# SQUID_Channel_DACS.net
KiCad netlist of a schematic drawn in Altium Designer
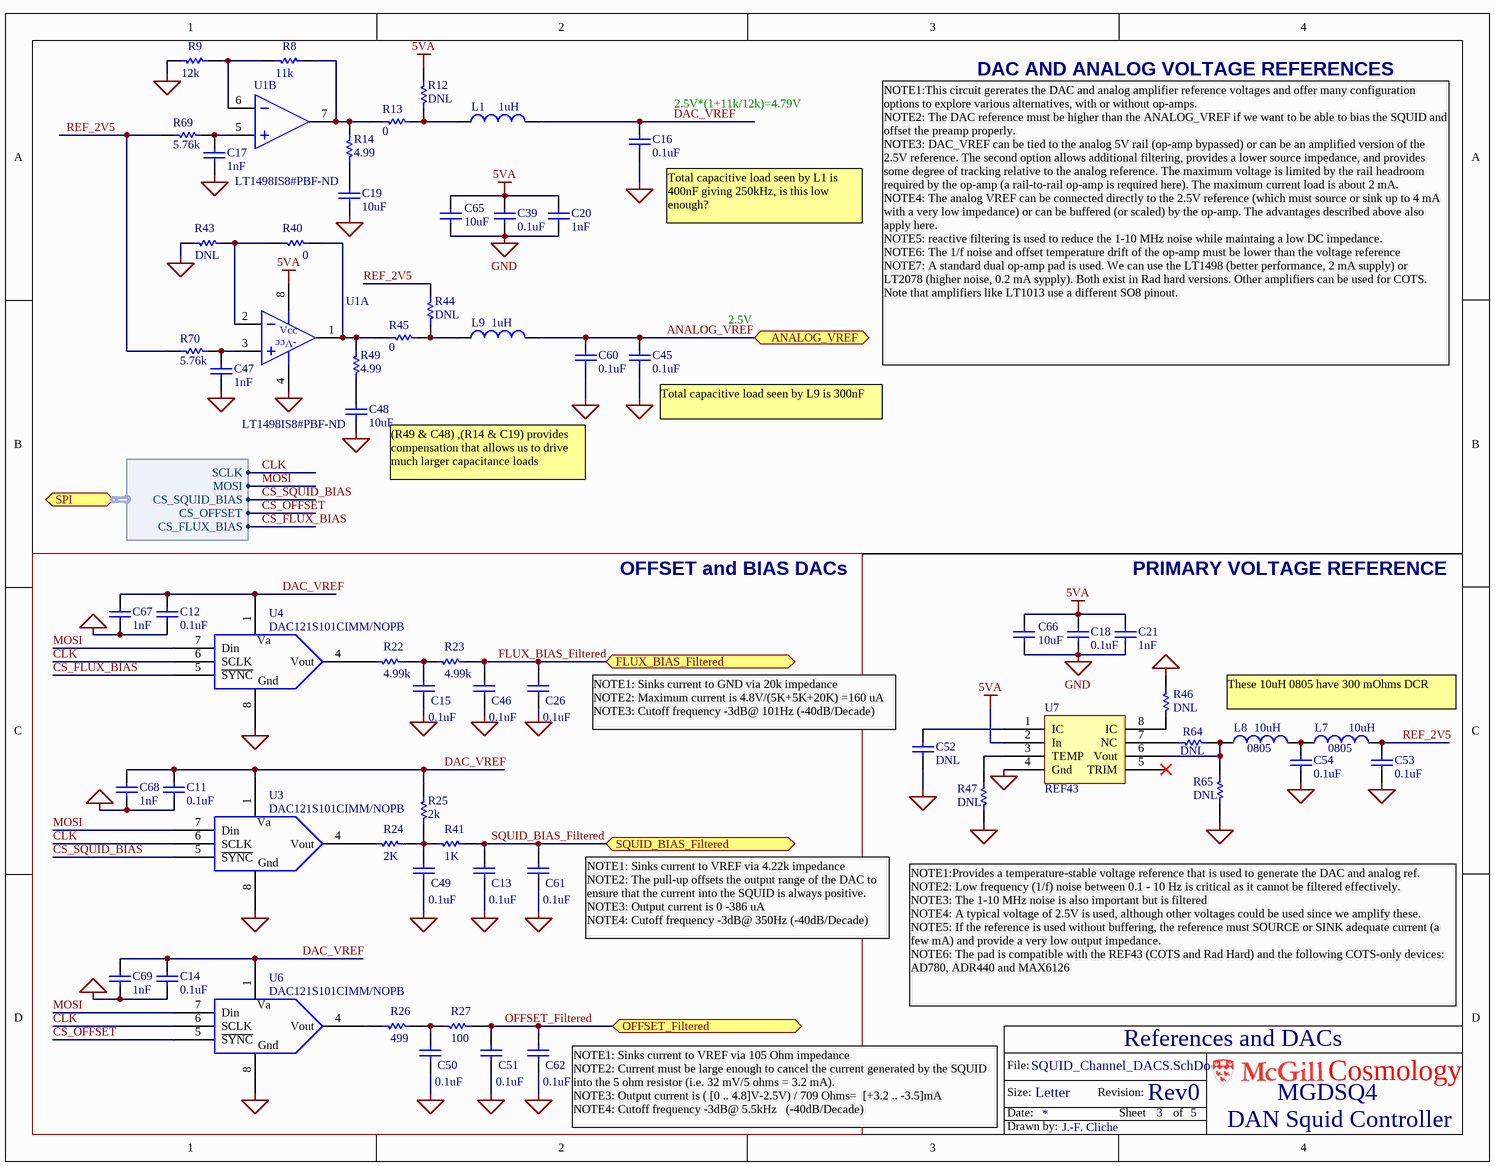
[diagram p0: SQUID_Channel_DACS.SchDoc]

(export (version "E")
  (design (tool "Eeschema 10.0.6"))
  (components
    (comp (ref "C11")
      (value "0.1uF")
      (footprint "0603")
      (description "Capacitor, Ceramic, 0603")
      (fields (field (name "MANUFACTURER") "Generic"))
      (libsource (lib "MiniSquidCtrl") (part "Cap0603"))
    )
    (comp (ref "C12")
      (value "0.1uF")
      (footprint "0603")
      (description "Capacitor, Ceramic, 0603")
      (fields (field (name "MANUFACTURER") "Generic"))
      (libsource (lib "MiniSquidCtrl") (part "Cap0603"))
    )
    (comp (ref "C13")
      (value "0.1uF")
      (footprint "0603")
      (description "Capacitor, Ceramic, 0603")
      (fields (field (name "MANUFACTURER") "Generic"))
      (libsource (lib "MiniSquidCtrl") (part "Cap0603"))
    )
    (comp (ref "C14")
      (value "0.1uF")
      (footprint "0603")
      (description "Capacitor, Ceramic, 0603")
      (fields (field (name "MANUFACTURER") "Generic"))
      (libsource (lib "MiniSquidCtrl") (part "Cap0603"))
    )
    (comp (ref "C15")
      (value "0.1uF")
      (footprint "0603")
      (description "Capacitor, Ceramic, 0603")
      (fields (field (name "MANUFACTURER") "Generic"))
      (libsource (lib "MiniSquidCtrl") (part "Cap0603"))
    )
    (comp (ref "C16")
      (value "0.1uF")
      (footprint "0603")
      (description "Capacitor, Ceramic, 0603")
      (fields (field (name "MANUFACTURER") "Generic"))
      (libsource (lib "MiniSquidCtrl") (part "Cap0603"))
    )
    (comp (ref "C17")
      (value "1nF")
      (footprint "0603")
      (description "Capacitor, Ceramic, 0603")
      (fields (field (name "MANUFACTURER") "Generic"))
      (libsource (lib "MiniSquidCtrl") (part "Cap0603"))
    )
    (comp (ref "C18")
      (value "0.1uF")
      (footprint "0603")
      (description "Capacitor, Ceramic, 0603")
      (fields (field (name "MANUFACTURER") "Generic"))
      (libsource (lib "MiniSquidCtrl") (part "Cap0603"))
    )
    (comp (ref "C19")
      (value "10uF")
      (footprint "0603")
      (description "Capacitor, Ceramic, 0603")
      (fields (field (name "MANUFACTURER") "Generic"))
      (libsource (lib "MiniSquidCtrl") (part "Cap0603"))
    )
    (comp (ref "C20")
      (value "1nF")
      (footprint "0603")
      (description "Capacitor, Ceramic, 0603")
      (fields (field (name "MANUFACTURER") "Generic"))
      (libsource (lib "MiniSquidCtrl") (part "Cap0603"))
    )
    (comp (ref "C21")
      (value "1nF")
      (footprint "0603")
      (description "Capacitor, Ceramic, 0603")
      (fields (field (name "MANUFACTURER") "Generic"))
      (libsource (lib "MiniSquidCtrl") (part "Cap0603"))
    )
    (comp (ref "C26")
      (value "0.1uF")
      (footprint "0603")
      (description "Capacitor, Ceramic, 0603")
      (fields (field (name "MANUFACTURER") "Generic"))
      (libsource (lib "MiniSquidCtrl") (part "Cap0603"))
    )
    (comp (ref "C39")
      (value "0.1uF")
      (footprint "0603")
      (description "Capacitor, Ceramic, 0603")
      (fields (field (name "MANUFACTURER") "Generic"))
      (libsource (lib "MiniSquidCtrl") (part "Cap0603"))
    )
    (comp (ref "C45")
      (value "0.1uF")
      (footprint "0603")
      (description "Capacitor, Ceramic, 0603")
      (fields (field (name "MANUFACTURER") "Generic"))
      (libsource (lib "MiniSquidCtrl") (part "Cap0603"))
    )
    (comp (ref "C46")
      (value "0.1uF")
      (footprint "0603")
      (description "Capacitor, Ceramic, 0603")
      (fields (field (name "MANUFACTURER") "Generic"))
      (libsource (lib "MiniSquidCtrl") (part "Cap0603"))
    )
    (comp (ref "C47")
      (value "1nF")
      (footprint "0603")
      (description "Capacitor, Ceramic, 0603")
      (fields (field (name "MANUFACTURER") "Generic"))
      (libsource (lib "MiniSquidCtrl") (part "Cap0603"))
    )
    (comp (ref "C48")
      (value "10uF")
      (footprint "0603")
      (description "Capacitor, Ceramic, 0603")
      (fields (field (name "MANUFACTURER") "Generic"))
      (libsource (lib "MiniSquidCtrl") (part "Cap0603"))
    )
    (comp (ref "C49")
      (value "0.1uF")
      (footprint "0603")
      (description "Capacitor, Ceramic, 0603")
      (fields (field (name "MANUFACTURER") "Generic"))
      (libsource (lib "MiniSquidCtrl") (part "Cap0603"))
    )
    (comp (ref "C50")
      (value "0.1uF")
      (footprint "0603")
      (description "Capacitor, Ceramic, 0603")
      (fields (field (name "MANUFACTURER") "Generic"))
      (libsource (lib "MiniSquidCtrl") (part "Cap0603"))
    )
    (comp (ref "C51")
      (value "0.1uF")
      (footprint "0603")
      (description "Capacitor, Ceramic, 0603")
      (fields (field (name "MANUFACTURER") "Generic"))
      (libsource (lib "MiniSquidCtrl") (part "Cap0603"))
    )
    (comp (ref "C52")
      (value "DNL")
      (footprint "0603")
      (description "Capacitor, Ceramic, 0603")
      (fields (field (name "MANUFACTURER") "Generic"))
      (libsource (lib "MiniSquidCtrl") (part "Cap0603"))
    )
    (comp (ref "C53")
      (value "0.1uF")
      (footprint "0603")
      (description "Capacitor, Ceramic, 0603")
      (fields (field (name "MANUFACTURER") "Generic"))
      (libsource (lib "MiniSquidCtrl") (part "Cap0603"))
    )
    (comp (ref "C54")
      (value "0.1uF")
      (footprint "0603")
      (description "Capacitor, Ceramic, 0603")
      (fields (field (name "MANUFACTURER") "Generic"))
      (libsource (lib "MiniSquidCtrl") (part "Cap0603"))
    )
    (comp (ref "C60")
      (value "0.1uF")
      (footprint "0603")
      (description "Capacitor, Ceramic, 0603")
      (fields (field (name "MANUFACTURER") "Generic"))
      (libsource (lib "MiniSquidCtrl") (part "Cap0603"))
    )
    (comp (ref "C61")
      (value "0.1uF")
      (footprint "0603")
      (description "Capacitor, Ceramic, 0603")
      (fields (field (name "MANUFACTURER") "Generic"))
      (libsource (lib "MiniSquidCtrl") (part "Cap0603"))
    )
    (comp (ref "C62")
      (value "0.1uF")
      (footprint "0603")
      (description "Capacitor, Ceramic, 0603")
      (fields (field (name "MANUFACTURER") "Generic"))
      (libsource (lib "MiniSquidCtrl") (part "Cap0603"))
    )
    (comp (ref "C65")
      (value "10uF")
      (footprint "CC3225-1210")
      (description "Capacitor, Ceramic, 1210")
      (fields (field (name "MANUFACTURER PART NUMBER") "1206YD106KAT2A") (field (name "VOLTAGE") "16V"))
      (libsource (lib "MiniSquidCtrl") (part "CAP 1210"))
    )
    (comp (ref "C66")
      (value "10uF")
      (footprint "CC3225-1210")
      (description "Capacitor, Ceramic, 1210")
      (fields (field (name "MANUFACTURER PART NUMBER") "1206YD106KAT2A") (field (name "VOLTAGE") "16V"))
      (libsource (lib "MiniSquidCtrl") (part "CAP 1210"))
    )
    (comp (ref "C67")
      (value "1nF")
      (footprint "0603")
      (description "Capacitor, Ceramic, 0603")
      (fields (field (name "MANUFACTURER") "Generic"))
      (libsource (lib "MiniSquidCtrl") (part "Cap0603"))
    )
    (comp (ref "C68")
      (value "1nF")
      (footprint "0603")
      (description "Capacitor, Ceramic, 0603")
      (fields (field (name "MANUFACTURER") "Generic"))
      (libsource (lib "MiniSquidCtrl") (part "Cap0603"))
    )
    (comp (ref "C69")
      (value "1nF")
      (footprint "0603")
      (description "Capacitor, Ceramic, 0603")
      (fields (field (name "MANUFACTURER") "Generic"))
      (libsource (lib "MiniSquidCtrl") (part "Cap0603"))
    )
    (comp (ref "L1")
      (value "1uH")
      (footprint "0603")
      (description "Inductor 0603")
      (fields (field (name "MANUFACTURER") "TDK Corporation"))
      (libsource (lib "MiniSquidCtrl") (part "Inductor0603"))
    )
    (comp (ref "L7")
      (value "10uH")
      (footprint "0805")
      (description "Inductor 0805")
      (fields (field (name "INDUCTANCE") "10uH") (field (name "MANUFACTURER") "TDK Corporation"))
      (libsource (lib "MiniSquidCtrl") (part "Inductor0603"))
    )
    (comp (ref "L8")
      (value "10uH")
      (footprint "0805")
      (description "Inductor 0805")
      (fields (field (name "INDUCTANCE") "10uH") (field (name "MANUFACTURER") "TDK Corporation"))
      (libsource (lib "MiniSquidCtrl") (part "Inductor0603"))
    )
    (comp (ref "L9")
      (value "1uH")
      (footprint "0603")
      (description "Inductor 0603")
      (fields (field (name "MANUFACTURER") "TDK Corporation"))
      (libsource (lib "MiniSquidCtrl") (part "Inductor0603"))
    )
    (comp (ref "R8")
      (value "11k")
      (footprint "0603")
      (description "RES 0603")
      (fields (field (name "MANUFACTURER") "Generic"))
      (libsource (lib "MiniSquidCtrl") (part "Res0603"))
    )
    (comp (ref "R9")
      (value "12k")
      (footprint "0603")
      (description "RES 0603")
      (fields (field (name "MANUFACTURER") "Generic"))
      (libsource (lib "MiniSquidCtrl") (part "RES 0603"))
    )
    (comp (ref "R12")
      (value "DNL")
      (footprint "0603")
      (description "RES 0603")
      (fields (field (name "MANUFACTURER") "Generic"))
      (libsource (lib "MiniSquidCtrl") (part "Res0603"))
    )
    (comp (ref "R13")
      (value "0")
      (footprint "0603")
      (description "RES 0603")
      (fields (field (name "MANUFACTURER") "Generic"))
      (libsource (lib "MiniSquidCtrl") (part "Res0603"))
    )
    (comp (ref "R14")
      (value "4.99")
      (footprint "0603")
      (description "RES 0603")
      (fields (field (name "MANUFACTURER") "Generic"))
      (libsource (lib "MiniSquidCtrl") (part "Res0603"))
    )
    (comp (ref "R22")
      (value "4.99k")
      (footprint "0603")
      (description "RES 0603")
      (fields (field (name "MANUFACTURER") "Generic"))
      (libsource (lib "MiniSquidCtrl") (part "Res0603"))
    )
    (comp (ref "R23")
      (value "4.99k")
      (footprint "0603")
      (description "RES 0603")
      (fields (field (name "MANUFACTURER") "Generic"))
      (libsource (lib "MiniSquidCtrl") (part "Res0603"))
    )
    (comp (ref "R24")
      (value "2K")
      (footprint "0603")
      (description "RES 0603")
      (fields (field (name "MANUFACTURER") "Generic") (field (name "Comment") "2k"))
      (libsource (lib "MiniSquidCtrl") (part "Res0603"))
    )
    (comp (ref "R25")
      (value "2k")
      (footprint "0603")
      (description "RES 0603")
      (fields (field (name "MANUFACTURER") "Generic"))
      (libsource (lib "MiniSquidCtrl") (part "Res0603"))
    )
    (comp (ref "R26")
      (value "499")
      (footprint "0603")
      (description "RES 0603")
      (fields (field (name "MANUFACTURER") "Generic"))
      (libsource (lib "MiniSquidCtrl") (part "Res0603"))
    )
    (comp (ref "R27")
      (value "100")
      (footprint "0603")
      (description "RES 0603")
      (fields (field (name "MANUFACTURER") "Generic"))
      (libsource (lib "MiniSquidCtrl") (part "Res0603"))
    )
    (comp (ref "R40")
      (value "0")
      (footprint "0603")
      (description "RES 0603")
      (fields (field (name "MANUFACTURER") "Generic"))
      (libsource (lib "MiniSquidCtrl") (part "Res0603"))
    )
    (comp (ref "R41")
      (value "1K")
      (footprint "0603")
      (description "RES 0603")
      (fields (field (name "MANUFACTURER") "Generic") (field (name "Comment") "1k"))
      (libsource (lib "MiniSquidCtrl") (part "Res0603"))
    )
    (comp (ref "R43")
      (value "DNL")
      (footprint "0603")
      (description "RES 0603")
      (fields (field (name "MANUFACTURER") "Generic"))
      (libsource (lib "MiniSquidCtrl") (part "RES 0603"))
    )
    (comp (ref "R44")
      (value "DNL")
      (footprint "0603")
      (description "RES 0603")
      (fields (field (name "MANUFACTURER") "Generic"))
      (libsource (lib "MiniSquidCtrl") (part "Res0603"))
    )
    (comp (ref "R45")
      (value "0")
      (footprint "0603")
      (description "RES 0603")
      (fields (field (name "MANUFACTURER") "Generic"))
      (libsource (lib "MiniSquidCtrl") (part "Res0603"))
    )
    (comp (ref "R46")
      (value "DNL")
      (footprint "0603")
      (description "RES 0603")
      (fields (field (name "TOLERANCE") "1%") (field (name "POWER") "1/10W"))
      (libsource (lib "MiniSquidCtrl") (part "RES 0603"))
    )
    (comp (ref "R47")
      (value "DNL")
      (footprint "0603")
      (description "RES 0603")
      (fields (field (name "MANUFACTURER") "Generic"))
      (libsource (lib "MiniSquidCtrl") (part "RES 0603"))
    )
    (comp (ref "R49")
      (value "4.99")
      (footprint "0603")
      (description "RES 0603")
      (fields (field (name "MANUFACTURER") "Generic"))
      (libsource (lib "MiniSquidCtrl") (part "Res0603"))
    )
    (comp (ref "R64")
      (value "DNL")
      (footprint "0603")
      (description "RES 0603")
      (fields (field (name "MANUFACTURER") "Generic"))
      (libsource (lib "MiniSquidCtrl") (part "RES 0603"))
    )
    (comp (ref "R65")
      (value "DNL")
      (footprint "0603")
      (description "RES 0603")
      (fields (field (name "MANUFACTURER") "Generic"))
      (libsource (lib "MiniSquidCtrl") (part "RES 0603"))
    )
    (comp (ref "R69")
      (value "5.76k")
      (footprint "0603")
      (description "RES 0603")
      (fields (field (name "MANUFACTURER") "Generic"))
      (libsource (lib "MiniSquidCtrl") (part "Res0603"))
    )
    (comp (ref "R70")
      (value "5.76k")
      (footprint "0603")
      (description "RES 0603")
      (fields (field (name "MANUFACTURER") "Generic"))
      (libsource (lib "MiniSquidCtrl") (part "Res0603"))
    )
    (comp (ref "U1")
      (value "LT1498IS8#PBF-ND")
      (footprint "SO8")
      (description "IC OP AMP DUAL 2CH LN 8-SOIC")
      (fields (field (name "MANUFACTURER") "National Semiconductor"))
      (libsource (lib "MiniSquidCtrl") (part "LMH6628"))
    )
    (comp (ref "U3")
      (value "DAC121S101CIMM/NOPB")
      (footprint "MSOP-8")
      (description "CONV D/A 12BIT MICROPWR 8MSOP")
      (fields (field (name "MANUFACTURER") "National Semiconductor"))
      (libsource (lib "MiniSquidCtrl") (part "DAC121S101CIMM/NOPB"))
    )
    (comp (ref "U4")
      (value "DAC121S101CIMM/NOPB")
      (footprint "MSOP-8")
      (description "CONV D/A 12BIT MICROPWR 8MSOP")
      (fields (field (name "MANUFACTURER") "National Semiconductor"))
      (libsource (lib "MiniSquidCtrl") (part "DAC121S101CIMM/NOPB"))
    )
    (comp (ref "U6")
      (value "DAC121S101CIMM/NOPB")
      (footprint "MSOP-8")
      (description "CONV D/A 12BIT MICROPWR 8MSOP")
      (fields (field (name "MANUFACTURER") "National Semiconductor"))
      (libsource (lib "MiniSquidCtrl") (part "DAC121S101CIMM/NOPB"))
    )
    (comp (ref "U7")
      (value "REF43")
      (footprint "SO8")
      (description "Voltage Referance")
      (libsource (lib "MiniSquidCtrl") (part "REF43"))
    )
  )
  (nets
    (net (code "2") (name "/ANALOG_VREF") (class "Default")
      (node (ref "C45") (pin "2") (pinfunction "2_2") (pintype "passive"))
      (node (ref "C60") (pin "2") (pinfunction "2_2") (pintype "passive"))
      (node (ref "L9") (pin "1") (pinfunction "1_1") (pintype "passive"))
    )
    (net (code "3") (name "/CLK") (class "Default")
      (node (ref "U3") (pin "6") (pinfunction "SCLK_6") (pintype "passive"))
      (node (ref "U4") (pin "6") (pinfunction "SCLK_6") (pintype "passive"))
      (node (ref "U6") (pin "6") (pinfunction "SCLK_6") (pintype "passive"))
    )
    (net (code "4") (name "/CS_FLUX_BIAS") (class "Default")
      (node (ref "U4") (pin "5") (pinfunction "~{SYNC}_5") (pintype "passive"))
    )
    (net (code "5") (name "/CS_OFFSET") (class "Default")
      (node (ref "U6") (pin "5") (pinfunction "~{SYNC}_5") (pintype "passive"))
    )
    (net (code "6") (name "/CS_SQUID_BIAS") (class "Default")
      (node (ref "U3") (pin "5") (pinfunction "~{SYNC}_5") (pintype "passive"))
    )
    (net (code "7") (name "/DAC_VREF") (class "Default")
      (node (ref "C11") (pin "1") (pinfunction "1_1") (pintype "passive"))
      (node (ref "C12") (pin "1") (pinfunction "1_1") (pintype "passive"))
      (node (ref "C14") (pin "2") (pinfunction "2_2") (pintype "passive"))
      (node (ref "C16") (pin "2") (pinfunction "2_2") (pintype "passive"))
      (node (ref "C67") (pin "2") (pinfunction "2_2") (pintype "passive"))
      (node (ref "C68") (pin "2") (pinfunction "2_2") (pintype "passive"))
      (node (ref "C69") (pin "2") (pinfunction "2_2") (pintype "passive"))
      (node (ref "L1") (pin "1") (pinfunction "1_1") (pintype "passive"))
      (node (ref "R25") (pin "2") (pinfunction "2_2") (pintype "passive"))
      (node (ref "U3") (pin "1") (pinfunction "Va_1") (pintype "passive"))
      (node (ref "U4") (pin "1") (pinfunction "Va_1") (pintype "passive"))
      (node (ref "U6") (pin "1") (pinfunction "Va_1") (pintype "passive"))
    )
    (net (code "8") (name "/FLUX_BIAS_Filtered") (class "Default")
      (node (ref "C26") (pin "1") (pinfunction "1_1") (pintype "passive"))
      (node (ref "C46") (pin "1") (pinfunction "1_1") (pintype "passive"))
      (node (ref "R23") (pin "2") (pinfunction "2_2") (pintype "passive"))
    )
    (net (code "9") (name "/MOSI") (class "Default")
      (node (ref "U3") (pin "7") (pinfunction "Din_7") (pintype "passive"))
      (node (ref "U4") (pin "7") (pinfunction "Din_7") (pintype "passive"))
      (node (ref "U6") (pin "7") (pinfunction "Din_7") (pintype "passive"))
    )
    (net (code "10") (name "/OFFSET_Filtered") (class "Default")
      (node (ref "C51") (pin "1") (pinfunction "1_1") (pintype "passive"))
      (node (ref "C62") (pin "1") (pinfunction "1_1") (pintype "passive"))
      (node (ref "R27") (pin "2") (pinfunction "2_2") (pintype "passive"))
    )
    (net (code "11") (name "/REF_2V5") (class "Default")
      (node (ref "C53") (pin "2") (pinfunction "2_2") (pintype "passive"))
      (node (ref "L7") (pin "1") (pinfunction "1_1") (pintype "passive"))
      (node (ref "R44") (pin "1") (pinfunction "1_1") (pintype "passive"))
      (node (ref "R69") (pin "2") (pinfunction "2_2") (pintype "passive"))
      (node (ref "R70") (pin "2") (pinfunction "2_2") (pintype "passive"))
    )
    (net (code "12") (name "/SQUID_BIAS_Filtered") (class "Default")
      (node (ref "C13") (pin "1") (pinfunction "1_1") (pintype "passive"))
      (node (ref "C61") (pin "1") (pinfunction "1_1") (pintype "passive"))
      (node (ref "R41") (pin "2") (pinfunction "2_2") (pintype "passive"))
    )
    (net (code "14") (name "5VA") (class "Default")
      (node (ref "C18") (pin "2") (pinfunction "2_2") (pintype "passive"))
      (node (ref "C20") (pin "2") (pinfunction "2_2") (pintype "passive"))
      (node (ref "C21") (pin "2") (pinfunction "2_2") (pintype "passive"))
      (node (ref "C39") (pin "2") (pinfunction "2_2") (pintype "passive"))
      (node (ref "C65") (pin "2") (pinfunction "2_2") (pintype "passive"))
      (node (ref "C66") (pin "2") (pinfunction "2_2") (pintype "passive"))
      (node (ref "R12") (pin "1") (pinfunction "1_1") (pintype "passive"))
      (node (ref "U1") (pin "8") (pinfunction "VDD_8") (pintype "passive"))
      (node (ref "U7") (pin "2") (pinfunction "In_2") (pintype "passive"))
    )
    (net (code "15") (name "GND") (class "Default")
      (node (ref "C11") (pin "2") (pinfunction "2_2") (pintype "passive"))
      (node (ref "C12") (pin "2") (pinfunction "2_2") (pintype "passive"))
      (node (ref "C13") (pin "2") (pinfunction "2_2") (pintype "passive"))
      (node (ref "C14") (pin "1") (pinfunction "1_1") (pintype "passive"))
      (node (ref "C15") (pin "2") (pinfunction "2_2") (pintype "passive"))
      (node (ref "C16") (pin "1") (pinfunction "1_1") (pintype "passive"))
      (node (ref "C17") (pin "1") (pinfunction "1_1") (pintype "passive"))
      (node (ref "C18") (pin "1") (pinfunction "1_1") (pintype "passive"))
      (node (ref "C19") (pin "1") (pinfunction "1_1") (pintype "passive"))
      (node (ref "C20") (pin "1") (pinfunction "1_1") (pintype "passive"))
      (node (ref "C21") (pin "1") (pinfunction "1_1") (pintype "passive"))
      (node (ref "C26") (pin "2") (pinfunction "2_2") (pintype "passive"))
      (node (ref "C39") (pin "1") (pinfunction "1_1") (pintype "passive"))
      (node (ref "C45") (pin "1") (pinfunction "1_1") (pintype "passive"))
      (node (ref "C46") (pin "2") (pinfunction "2_2") (pintype "passive"))
      (node (ref "C47") (pin "1") (pinfunction "1_1") (pintype "passive"))
      (node (ref "C48") (pin "1") (pinfunction "1_1") (pintype "passive"))
      (node (ref "C49") (pin "2") (pinfunction "2_2") (pintype "passive"))
      (node (ref "C50") (pin "2") (pinfunction "2_2") (pintype "passive"))
      (node (ref "C51") (pin "2") (pinfunction "2_2") (pintype "passive"))
      (node (ref "C52") (pin "1") (pinfunction "1_1") (pintype "passive"))
      (node (ref "C53") (pin "1") (pinfunction "1_1") (pintype "passive"))
      (node (ref "C54") (pin "1") (pinfunction "1_1") (pintype "passive"))
      (node (ref "C60") (pin "1") (pinfunction "1_1") (pintype "passive"))
      (node (ref "C61") (pin "2") (pinfunction "2_2") (pintype "passive"))
      (node (ref "C62") (pin "2") (pinfunction "2_2") (pintype "passive"))
      (node (ref "C65") (pin "1") (pinfunction "1_1") (pintype "passive"))
      (node (ref "C66") (pin "1") (pinfunction "1_1") (pintype "passive"))
      (node (ref "C67") (pin "1") (pinfunction "1_1") (pintype "passive"))
      (node (ref "C68") (pin "1") (pinfunction "1_1") (pintype "passive"))
      (node (ref "C69") (pin "1") (pinfunction "1_1") (pintype "passive"))
      (node (ref "R43") (pin "2") (pinfunction "2_2") (pintype "passive"))
      (node (ref "R46") (pin "2") (pinfunction "2_2") (pintype "passive"))
      (node (ref "R47") (pin "1") (pinfunction "1_1") (pintype "passive"))
      (node (ref "R65") (pin "1") (pinfunction "1_1") (pintype "passive"))
      (node (ref "R9") (pin "2") (pinfunction "2_2") (pintype "passive"))
      (node (ref "U1") (pin "4") (pinfunction "GND_4") (pintype "passive"))
      (node (ref "U3") (pin "8") (pinfunction "Gnd_8") (pintype "passive"))
      (node (ref "U4") (pin "8") (pinfunction "Gnd_8") (pintype "passive"))
      (node (ref "U6") (pin "8") (pinfunction "Gnd_8") (pintype "passive"))
      (node (ref "U7") (pin "4") (pinfunction "Gnd_4") (pintype "passive"))
    )
    (net (code "16") (name "Net-(C15-Pad1)") (class "Default")
      (node (ref "C15") (pin "1") (pinfunction "1_1") (pintype "passive"))
      (node (ref "R22") (pin "2") (pinfunction "2_2") (pintype "passive"))
      (node (ref "R23") (pin "1") (pinfunction "1_1") (pintype "passive"))
    )
    (net (code "17") (name "Net-(C19-Pad2)") (class "Default")
      (node (ref "C19") (pin "2") (pinfunction "2_2") (pintype "passive"))
      (node (ref "R14") (pin "2") (pinfunction "2_2") (pintype "passive"))
    )
    (net (code "18") (name "Net-(C48-Pad2)") (class "Default")
      (node (ref "C48") (pin "2") (pinfunction "2_2") (pintype "passive"))
      (node (ref "R49") (pin "2") (pinfunction "2_2") (pintype "passive"))
    )
    (net (code "19") (name "Net-(C49-Pad1)") (class "Default")
      (node (ref "C49") (pin "1") (pinfunction "1_1") (pintype "passive"))
      (node (ref "R24") (pin "2") (pinfunction "2_2") (pintype "passive"))
      (node (ref "R25") (pin "1") (pinfunction "1_1") (pintype "passive"))
      (node (ref "R41") (pin "1") (pinfunction "1_1") (pintype "passive"))
    )
    (net (code "20") (name "Net-(C50-Pad1)") (class "Default")
      (node (ref "C50") (pin "1") (pinfunction "1_1") (pintype "passive"))
      (node (ref "R26") (pin "2") (pinfunction "2_2") (pintype "passive"))
      (node (ref "R27") (pin "1") (pinfunction "1_1") (pintype "passive"))
    )
    (net (code "21") (name "Net-(C52-Pad2)") (class "Default")
      (node (ref "C52") (pin "2") (pinfunction "2_2") (pintype "passive"))
      (node (ref "U7") (pin "1") (pinfunction "IC_1") (pintype "passive"))
    )
    (net (code "22") (name "Net-(C54-Pad2)") (class "Default")
      (node (ref "C54") (pin "2") (pinfunction "2_2") (pintype "passive"))
      (node (ref "L7") (pin "2") (pinfunction "2_2") (pintype "passive"))
      (node (ref "L8") (pin "1") (pinfunction "1_1") (pintype "passive"))
    )
    (net (code "23") (name "Net-(L1-Pad2)") (class "Default")
      (node (ref "L1") (pin "2") (pinfunction "2_2") (pintype "passive"))
      (node (ref "R12") (pin "2") (pinfunction "2_2") (pintype "passive"))
      (node (ref "R13") (pin "2") (pinfunction "2_2") (pintype "passive"))
    )
    (net (code "24") (name "Net-(L9-Pad2)") (class "Default")
      (node (ref "L9") (pin "2") (pinfunction "2_2") (pintype "passive"))
      (node (ref "R44") (pin "2") (pinfunction "2_2") (pintype "passive"))
      (node (ref "R45") (pin "2") (pinfunction "2_2") (pintype "passive"))
    )
    (net (code "25") (name "Net-(R46-Pad1)") (class "Default")
      (node (ref "R46") (pin "1") (pinfunction "1_1") (pintype "passive"))
      (node (ref "U7") (pin "8") (pinfunction "IC_8") (pintype "passive"))
    )
    (net (code "26") (name "Net-(U1A-IN+)") (class "Default")
      (node (ref "C47") (pin "2") (pinfunction "2_2") (pintype "passive"))
      (node (ref "R70") (pin "1") (pinfunction "1_1") (pintype "passive"))
      (node (ref "U1") (pin "3") (pinfunction "IN+_3") (pintype "passive"))
    )
    (net (code "27") (name "Net-(U1A-IN-)") (class "Default")
      (node (ref "R40") (pin "1") (pinfunction "1_1") (pintype "passive"))
      (node (ref "R43") (pin "1") (pinfunction "1_1") (pintype "passive"))
      (node (ref "U1") (pin "2") (pinfunction "IN-_2") (pintype "passive"))
    )
    (net (code "28") (name "Net-(U1A-OUT)") (class "Default")
      (node (ref "R40") (pin "2") (pinfunction "2_2") (pintype "passive"))
      (node (ref "R45") (pin "1") (pinfunction "1_1") (pintype "passive"))
      (node (ref "R49") (pin "1") (pinfunction "1_1") (pintype "passive"))
      (node (ref "U1") (pin "1") (pinfunction "OUT_1") (pintype "passive"))
    )
    (net (code "29") (name "Net-(U1B-IN+)") (class "Default")
      (node (ref "C17") (pin "2") (pinfunction "2_2") (pintype "passive"))
      (node (ref "R69") (pin "1") (pinfunction "1_1") (pintype "passive"))
      (node (ref "U1") (pin "5") (pinfunction "IN+_5") (pintype "passive"))
    )
    (net (code "30") (name "Net-(U1B-IN-)") (class "Default")
      (node (ref "R8") (pin "1") (pinfunction "1_1") (pintype "passive"))
      (node (ref "R9") (pin "1") (pinfunction "1_1") (pintype "passive"))
      (node (ref "U1") (pin "6") (pinfunction "IN-_6") (pintype "passive"))
    )
    (net (code "31") (name "Net-(U1B-OUT)") (class "Default")
      (node (ref "R13") (pin "1") (pinfunction "1_1") (pintype "passive"))
      (node (ref "R14") (pin "1") (pinfunction "1_1") (pintype "passive"))
      (node (ref "R8") (pin "2") (pinfunction "2_2") (pintype "passive"))
      (node (ref "U1") (pin "7") (pinfunction "OUT_7") (pintype "passive"))
    )
    (net (code "32") (name "Net-(U3-Vout)") (class "Default")
      (node (ref "R24") (pin "1") (pinfunction "1_1") (pintype "passive"))
      (node (ref "U3") (pin "4") (pinfunction "Vout_4") (pintype "passive"))
    )
    (net (code "33") (name "Net-(U4-Vout)") (class "Default")
      (node (ref "R22") (pin "1") (pinfunction "1_1") (pintype "passive"))
      (node (ref "U4") (pin "4") (pinfunction "Vout_4") (pintype "passive"))
    )
    (net (code "34") (name "Net-(U6-Vout)") (class "Default")
      (node (ref "R26") (pin "1") (pinfunction "1_1") (pintype "passive"))
      (node (ref "U6") (pin "4") (pinfunction "Vout_4") (pintype "passive"))
    )
    (net (code "35") (name "Net-(U7-NC)") (class "Default")
      (node (ref "R64") (pin "2") (pinfunction "2_2") (pintype "passive"))
      (node (ref "U7") (pin "7") (pinfunction "NC_7") (pintype "passive"))
    )
    (net (code "36") (name "Net-(U7-TEMP)") (class "Default")
      (node (ref "R47") (pin "2") (pinfunction "2_2") (pintype "passive"))
      (node (ref "U7") (pin "3") (pinfunction "TEMP_3") (pintype "passive"))
    )
    (net (code "37") (name "Net-(U7-Vout)") (class "Default")
      (node (ref "L8") (pin "2") (pinfunction "2_2") (pintype "passive"))
      (node (ref "R64") (pin "1") (pinfunction "1_1") (pintype "passive"))
      (node (ref "R65") (pin "2") (pinfunction "2_2") (pintype "passive"))
      (node (ref "U7") (pin "6") (pinfunction "Vout_6") (pintype "passive"))
    )
    (net (code "38") (name "unconnected-(U3-NC-Pad2)") (class "Default")
      (node (ref "U3") (pin "2") (pinfunction "NC_2") (pintype "passive"))
    )
    (net (code "39") (name "unconnected-(U3-NC-Pad3)") (class "Default")
      (node (ref "U3") (pin "3") (pinfunction "NC_3") (pintype "passive"))
    )
    (net (code "40") (name "unconnected-(U4-NC-Pad2)") (class "Default")
      (node (ref "U4") (pin "2") (pinfunction "NC_2") (pintype "passive"))
    )
    (net (code "41") (name "unconnected-(U4-NC-Pad3)") (class "Default")
      (node (ref "U4") (pin "3") (pinfunction "NC_3") (pintype "passive"))
    )
    (net (code "42") (name "unconnected-(U6-NC-Pad2)") (class "Default")
      (node (ref "U6") (pin "2") (pinfunction "NC_2") (pintype "passive"))
    )
    (net (code "43") (name "unconnected-(U6-NC-Pad3)") (class "Default")
      (node (ref "U6") (pin "3") (pinfunction "NC_3") (pintype "passive"))
    )
    (net (code "44") (name "unconnected-(U7-TRIM-Pad5)") (class "Default")
      (node (ref "U7") (pin "5") (pinfunction "TRIM_5") (pintype "passive+no_connect"))
    )
  )
)
